# Connector_0.net
KiCad netlist of a schematic drawn in Altium Designer
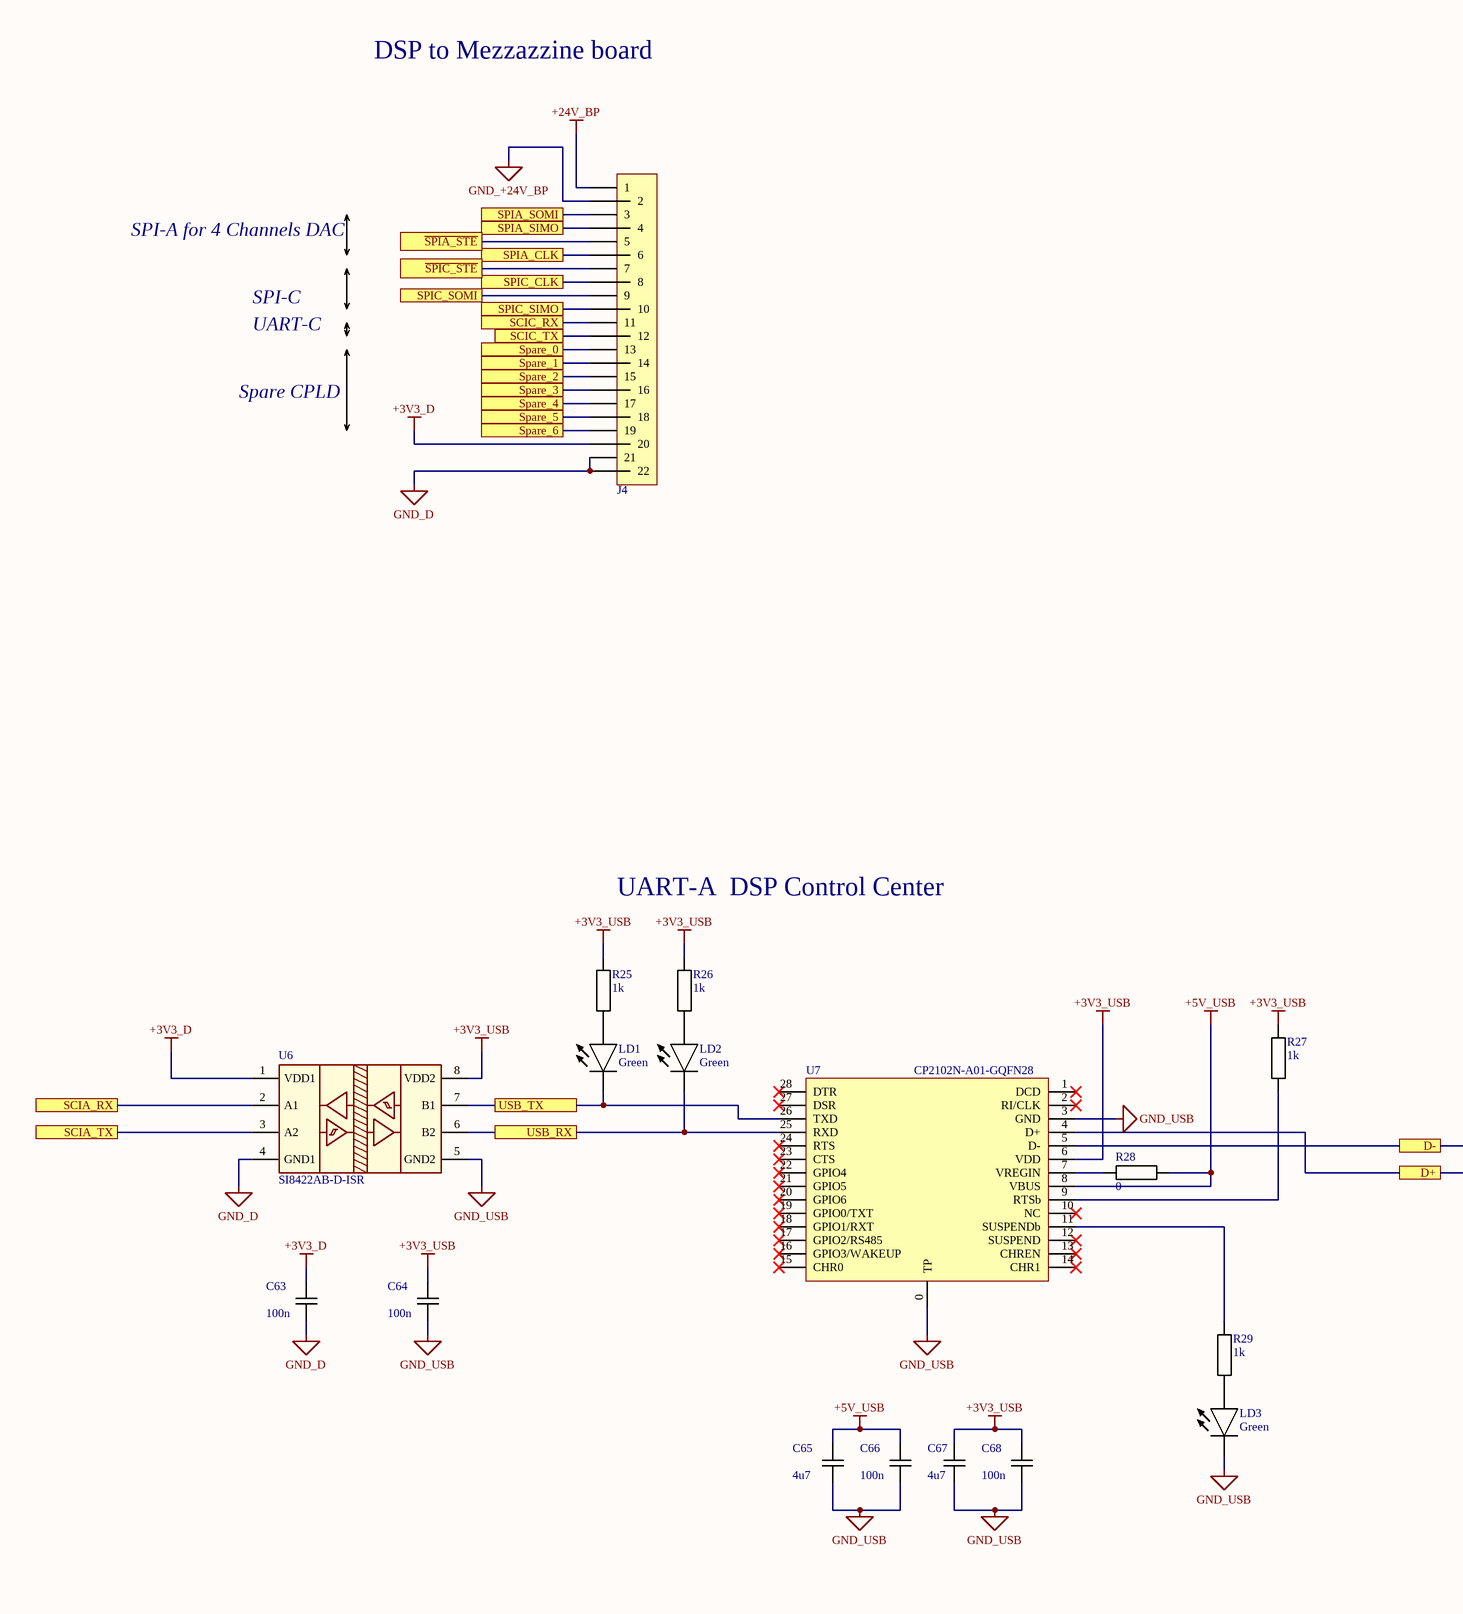
[diagram p0: Connector_0.SchDoc, left]
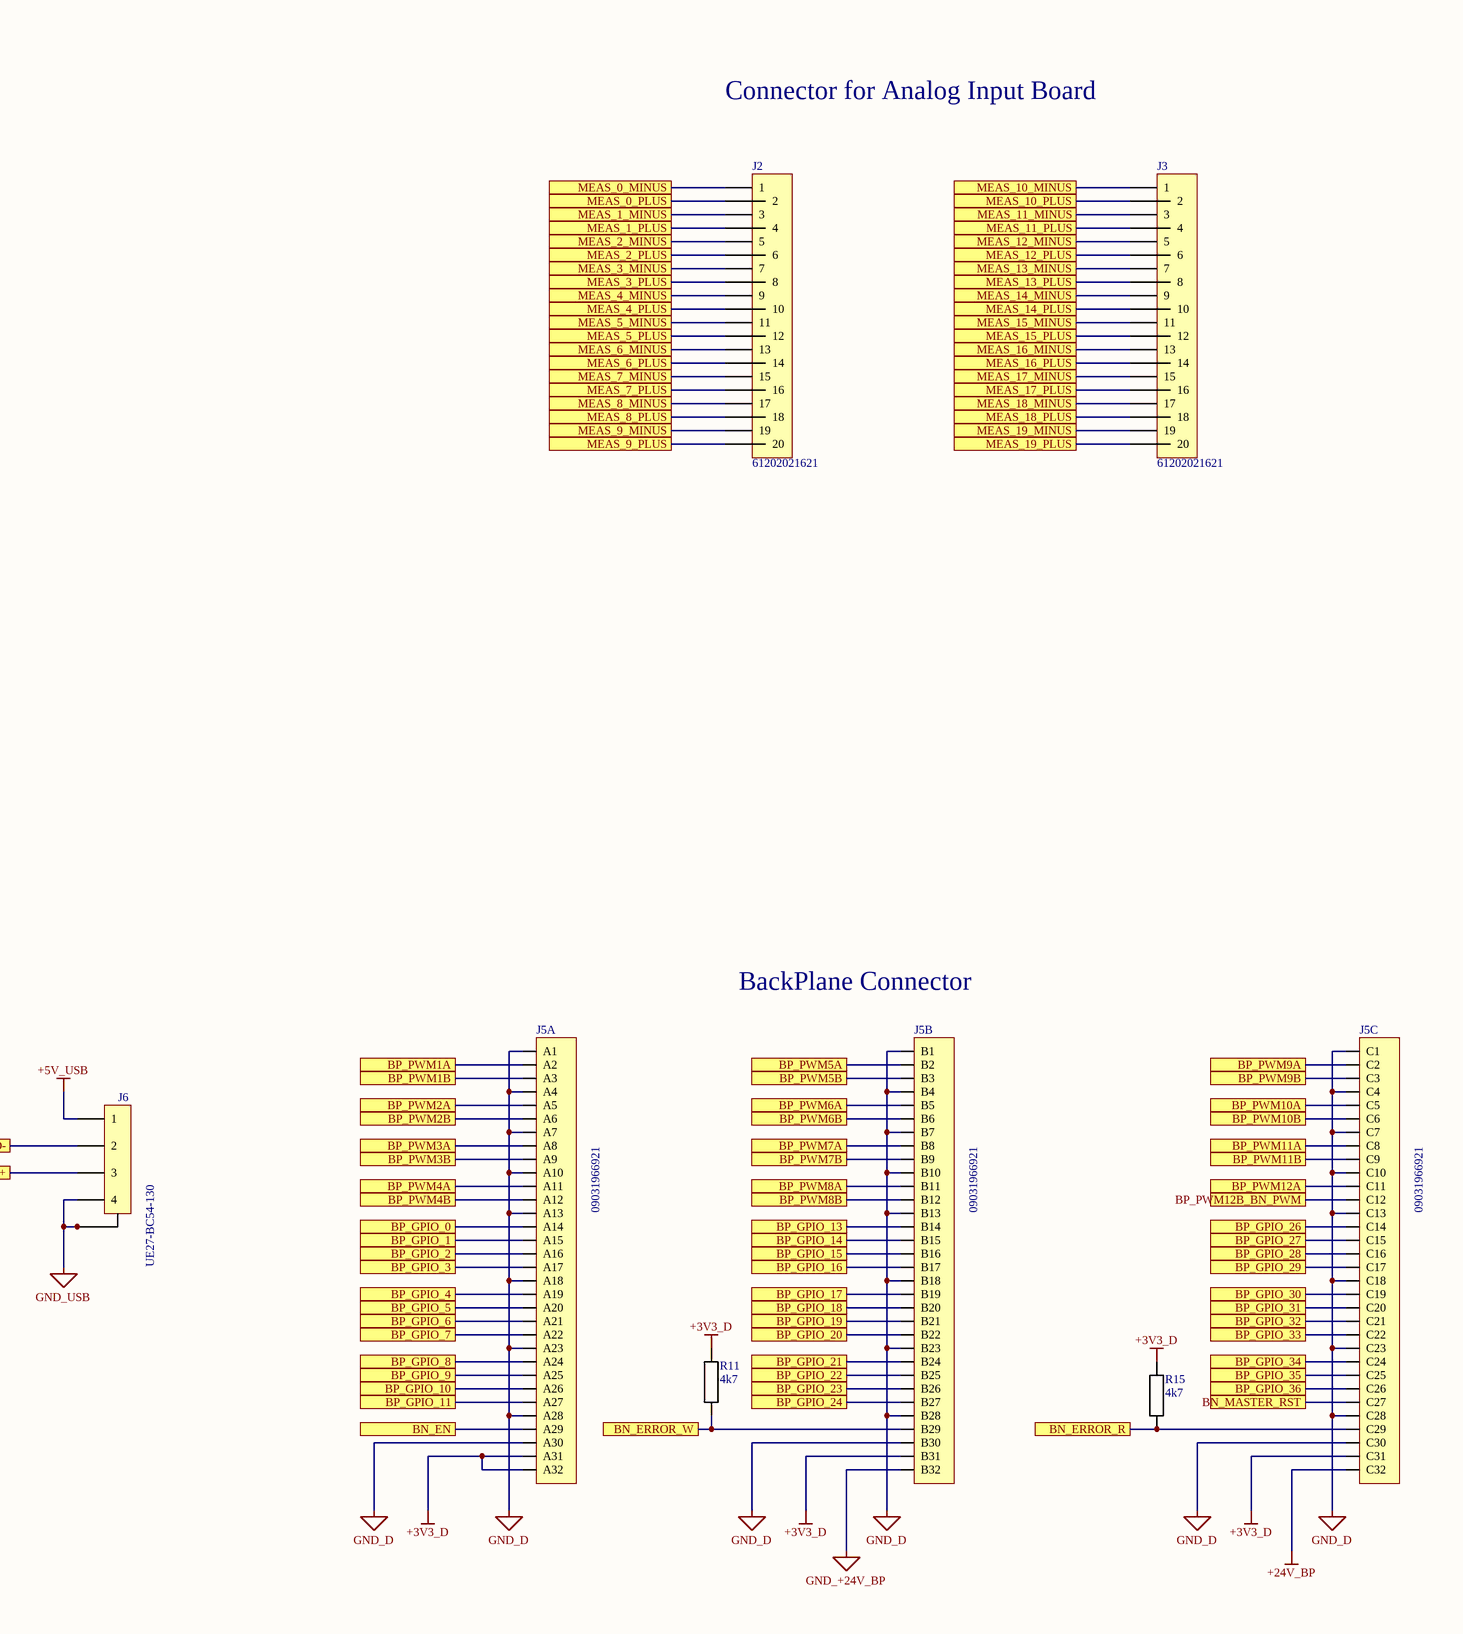
[diagram p1: Connector_0.SchDoc, right]

(export (version "E")
  (design (tool "Eeschema 10.0.6"))
  (components
    (comp (ref "C63")
      (value "100n")
      (footprint "CAPACITOR 1608 REFLOW")
      (description "Capacitor X7R 10% 50V 1608(0603)")
      (libsource (lib "Capacitor") (part "Capacitor"))
    )
    (comp (ref "C64")
      (value "100n")
      (footprint "CAPACITOR 1608 REFLOW")
      (description "Capacitor X7R 10% 50V 1608(0603)")
      (libsource (lib "Capacitor") (part "Capacitor"))
    )
    (comp (ref "C65")
      (value "4u7")
      (footprint "CAPACITOR 2012 REFLOW")
      (description "Capacitor X7R 10% 10V 2012(0805)")
      (libsource (lib "Capacitor") (part "Capacitor"))
    )
    (comp (ref "C66")
      (value "100n")
      (footprint "CAPACITOR 1608 REFLOW")
      (description "Capacitor X7R 10% 50V 1608(0603)")
      (libsource (lib "Capacitor") (part "Capacitor"))
    )
    (comp (ref "C67")
      (value "4u7")
      (footprint "CAPACITOR 2012 REFLOW")
      (description "Capacitor X7R 10% 10V 2012(0805)")
      (libsource (lib "Capacitor") (part "Capacitor"))
    )
    (comp (ref "C68")
      (value "100n")
      (footprint "CAPACITOR 1608 REFLOW")
      (description "Capacitor X7R 10% 50V 1608(0603)")
      (libsource (lib "Capacitor") (part "Capacitor"))
    )
    (comp (ref "J2")
      (value "61202021621")
      (footprint "FlatCable2x10 2.54MM Straight TH")
      (description "FlatCable2x10")
      (fields (field (name "MANUFACTURER") "Wurth Elektronik"))
      (libsource (lib "Connector") (part "FlatCable2x10"))
    )
    (comp (ref "J3")
      (value "61202021621")
      (footprint "FlatCable2x10 2.54MM Straight TH")
      (description "FlatCable2x10")
      (fields (field (name "MANUFACTURER") "Wurth Elektronik"))
      (libsource (lib "Connector") (part "FlatCable2x10"))
    )
    (comp (ref "J4")
      (value "*")
      (footprint "PinHeader2x11 P2.54 A")
      (description "Plug connector")
      (libsource (lib "PinHeader") (part "PinHeader2x11"))
    )
    (comp (ref "J5")
      (value "09031966921")
      (footprint "DIN41612 MALE 3X32 ABC R90")
      (description "DIN41612 MALE 3X32 ABC R90")
      (fields (field (name "MANUFACTURER") "Harting"))
      (libsource (lib "Connector") (part "DIN41612 MALE 3X32 ABC R90"))
    )
    (comp (ref "J6")
      (value "UE27-BC54-130")
      (footprint "USB-B TH AMPHENOL UE27-BC54-130")
      (description "USB-B-TH-AMPHENOL UE27-BC54-130")
      (fields (field (name "MANUFACTURER") "Amphenol ICC"))
      (libsource (lib "Connector") (part "USB-B-TH-AMPHENOL UE27-BC54-130"))
    )
    (comp (ref "LD1")
      (value "Green")
      (footprint "LED 2012 REFLOW")
      (description "LED generic")
      (libsource (lib "Diode") (part "LED"))
    )
    (comp (ref "LD2")
      (value "Green")
      (footprint "LED 2012 REFLOW")
      (description "LED generic")
      (libsource (lib "Diode") (part "LED"))
    )
    (comp (ref "LD3")
      (value "Green")
      (footprint "LED 2012 REFLOW")
      (description "LED generic")
      (libsource (lib "Diode") (part "LED"))
    )
    (comp (ref "R11")
      (value "4k7")
      (footprint "RESISTOR 1608 REFLOW")
      (description "Resistor 1% 50V 100mW 1608(0603)")
      (libsource (lib "Resistor") (part "Resistor"))
    )
    (comp (ref "R15")
      (value "4k7")
      (footprint "RESISTOR 1608 REFLOW")
      (description "Resistor 1% 50V 100mW 1608(0603)")
      (libsource (lib "Resistor") (part "Resistor"))
    )
    (comp (ref "R25")
      (value "1k")
      (footprint "RESISTOR 1608 REFLOW")
      (description "Resistor 1% 50V 100mW 1608(0603)")
      (libsource (lib "Resistor") (part "Resistor"))
    )
    (comp (ref "R26")
      (value "1k")
      (footprint "RESISTOR 1608 REFLOW")
      (description "Resistor 1% 50V 100mW 1608(0603)")
      (libsource (lib "Resistor") (part "Resistor"))
    )
    (comp (ref "R27")
      (value "1k")
      (footprint "RESISTOR 1608 REFLOW")
      (description "Resistor 1% 50V 100mW 1608(0603)")
      (libsource (lib "Resistor") (part "Resistor"))
    )
    (comp (ref "R28")
      (value "0")
      (footprint "RESISTOR 1608 REFLOW")
      (description "Resistor 1% 50V 100mW 1608(0603)")
      (libsource (lib "Resistor") (part "Resistor"))
    )
    (comp (ref "R29")
      (value "1k")
      (footprint "RESISTOR 1608 REFLOW")
      (description "Resistor 1% 50V 100mW 1608(0603)")
      (libsource (lib "Resistor") (part "Resistor"))
    )
    (comp (ref "U6")
      (value "SI8422AB-D-ISR")
      (footprint "SO8 P1.27 C4.0X5.0 H1.75")
      (description "Optocoupler")
      (fields (field (name "MANUFACTURER") "Silicon Labs"))
      (libsource (lib "Optocoupler") (part "SI8422"))
    )
    (comp (ref "U7")
      (value "CP2102N-A01-GQFN28")
      (footprint "QFN28 P0.5 T3.4X3.4 C5.0X5.0 H0.8")
      (description "USBXpress")
      (fields (field (name "MANUFACTURER") "Silicon Labs"))
      (libsource (lib "IntegratedCircuit") (part "CP2102N"))
    )
  )
  (nets
    (net (code "1") (name "+3V3_D") (class "Default")
      (node (ref "C63") (pin "2") (pinfunction "2_2") (pintype "passive"))
      (node (ref "J4") (pin "20") (pinfunction "20_20") (pintype "passive"))
      (node (ref "J5") (pin "A31") (pinfunction "A31_A31") (pintype "passive"))
      (node (ref "J5") (pin "A32") (pinfunction "A32_A32") (pintype "passive"))
      (node (ref "J5") (pin "B31") (pinfunction "B31_B31") (pintype "passive"))
      (node (ref "J5") (pin "C31") (pinfunction "C31_C31") (pintype "passive"))
      (node (ref "R11") (pin "2") (pinfunction "2_2") (pintype "passive"))
      (node (ref "R15") (pin "2") (pinfunction "2_2") (pintype "passive"))
      (node (ref "U6") (pin "1") (pinfunction "VDD1_1") (pintype "passive"))
    )
    (net (code "2") (name "+3V3_USB") (class "Default")
      (node (ref "C64") (pin "2") (pinfunction "2_2") (pintype "passive"))
      (node (ref "C67") (pin "2") (pinfunction "2_2") (pintype "passive"))
      (node (ref "C68") (pin "2") (pinfunction "2_2") (pintype "passive"))
      (node (ref "R25") (pin "2") (pinfunction "2_2") (pintype "passive"))
      (node (ref "R26") (pin "2") (pinfunction "2_2") (pintype "passive"))
      (node (ref "R27") (pin "2") (pinfunction "2_2") (pintype "passive"))
      (node (ref "U6") (pin "8") (pinfunction "VDD2_8") (pintype "power_in"))
      (node (ref "U7") (pin "6") (pinfunction "VDD_6") (pintype "passive"))
    )
    (net (code "3") (name "+5V_USB") (class "Default")
      (node (ref "C65") (pin "2") (pinfunction "2_2") (pintype "passive"))
      (node (ref "C66") (pin "2") (pinfunction "2_2") (pintype "passive"))
      (node (ref "J6") (pin "1") (pinfunction "1_1") (pintype "passive"))
      (node (ref "R28") (pin "1") (pinfunction "1_1") (pintype "passive"))
      (node (ref "U7") (pin "8") (pinfunction "VBUS_8") (pintype "passive"))
    )
    (net (code "4") (name "+24V_BP") (class "Default")
      (node (ref "J4") (pin "1") (pinfunction "1_1") (pintype "passive"))
      (node (ref "J5") (pin "C32") (pinfunction "C32_C32") (pintype "passive"))
    )
    (net (code "5") (name "/BN_EN") (class "Default")
      (node (ref "J5") (pin "A29") (pinfunction "A29_A29") (pintype "passive"))
    )
    (net (code "6") (name "/BN_ERROR_R") (class "Default")
      (node (ref "J5") (pin "C29") (pinfunction "C29_C29") (pintype "passive"))
      (node (ref "R15") (pin "1") (pinfunction "1_1") (pintype "passive"))
    )
    (net (code "7") (name "/BN_ERROR_W") (class "Default")
      (node (ref "J5") (pin "B29") (pinfunction "B29_B29") (pintype "passive"))
      (node (ref "R11") (pin "1") (pinfunction "1_1") (pintype "passive"))
    )
    (net (code "8") (name "/BN_MASTER_RST") (class "Default")
      (node (ref "J5") (pin "C27") (pinfunction "C27_C27") (pintype "passive"))
    )
    (net (code "9") (name "/BP_GPIO_0") (class "Default")
      (node (ref "J5") (pin "A14") (pinfunction "A14_A14") (pintype "passive"))
    )
    (net (code "10") (name "/BP_GPIO_1") (class "Default")
      (node (ref "J5") (pin "A15") (pinfunction "A15_A15") (pintype "passive"))
    )
    (net (code "11") (name "/BP_GPIO_2") (class "Default")
      (node (ref "J5") (pin "A16") (pinfunction "A16_A16") (pintype "passive"))
    )
    (net (code "12") (name "/BP_GPIO_3") (class "Default")
      (node (ref "J5") (pin "A17") (pinfunction "A17_A17") (pintype "passive"))
    )
    (net (code "13") (name "/BP_GPIO_4") (class "Default")
      (node (ref "J5") (pin "A19") (pinfunction "A19_A19") (pintype "passive"))
    )
    (net (code "14") (name "/BP_GPIO_5") (class "Default")
      (node (ref "J5") (pin "A20") (pinfunction "A20_A20") (pintype "passive"))
    )
    (net (code "15") (name "/BP_GPIO_6") (class "Default")
      (node (ref "J5") (pin "A21") (pinfunction "A21_A21") (pintype "passive"))
    )
    (net (code "16") (name "/BP_GPIO_7") (class "Default")
      (node (ref "J5") (pin "A22") (pinfunction "A22_A22") (pintype "passive"))
    )
    (net (code "17") (name "/BP_GPIO_8") (class "Default")
      (node (ref "J5") (pin "A24") (pinfunction "A24_A24") (pintype "passive"))
    )
    (net (code "18") (name "/BP_GPIO_9") (class "Default")
      (node (ref "J5") (pin "A25") (pinfunction "A25_A25") (pintype "passive"))
    )
    (net (code "19") (name "/BP_GPIO_10") (class "Default")
      (node (ref "J5") (pin "A26") (pinfunction "A26_A26") (pintype "passive"))
    )
    (net (code "20") (name "/BP_GPIO_11") (class "Default")
      (node (ref "J5") (pin "A27") (pinfunction "A27_A27") (pintype "passive"))
    )
    (net (code "21") (name "/BP_GPIO_13") (class "Default")
      (node (ref "J5") (pin "B14") (pinfunction "B14_B14") (pintype "passive"))
    )
    (net (code "22") (name "/BP_GPIO_14") (class "Default")
      (node (ref "J5") (pin "B15") (pinfunction "B15_B15") (pintype "passive"))
    )
    (net (code "23") (name "/BP_GPIO_15") (class "Default")
      (node (ref "J5") (pin "B16") (pinfunction "B16_B16") (pintype "passive"))
    )
    (net (code "24") (name "/BP_GPIO_16") (class "Default")
      (node (ref "J5") (pin "B17") (pinfunction "B17_B17") (pintype "passive"))
    )
    (net (code "25") (name "/BP_GPIO_17") (class "Default")
      (node (ref "J5") (pin "B19") (pinfunction "B19_B19") (pintype "passive"))
    )
    (net (code "26") (name "/BP_GPIO_18") (class "Default")
      (node (ref "J5") (pin "B20") (pinfunction "B20_B20") (pintype "passive"))
    )
    (net (code "27") (name "/BP_GPIO_19") (class "Default")
      (node (ref "J5") (pin "B21") (pinfunction "B21_B21") (pintype "passive"))
    )
    (net (code "28") (name "/BP_GPIO_20") (class "Default")
      (node (ref "J5") (pin "B22") (pinfunction "B22_B22") (pintype "passive"))
    )
    (net (code "29") (name "/BP_GPIO_21") (class "Default")
      (node (ref "J5") (pin "B24") (pinfunction "B24_B24") (pintype "passive"))
    )
    (net (code "30") (name "/BP_GPIO_22") (class "Default")
      (node (ref "J5") (pin "B25") (pinfunction "B25_B25") (pintype "passive"))
    )
    (net (code "31") (name "/BP_GPIO_23") (class "Default")
      (node (ref "J5") (pin "B26") (pinfunction "B26_B26") (pintype "passive"))
    )
    (net (code "32") (name "/BP_GPIO_24") (class "Default")
      (node (ref "J5") (pin "B27") (pinfunction "B27_B27") (pintype "passive"))
    )
    (net (code "33") (name "/BP_GPIO_26") (class "Default")
      (node (ref "J5") (pin "C14") (pinfunction "C14_C14") (pintype "passive"))
    )
    (net (code "34") (name "/BP_GPIO_27") (class "Default")
      (node (ref "J5") (pin "C15") (pinfunction "C15_C15") (pintype "passive"))
    )
    (net (code "35") (name "/BP_GPIO_28") (class "Default")
      (node (ref "J5") (pin "C16") (pinfunction "C16_C16") (pintype "passive"))
    )
    (net (code "36") (name "/BP_GPIO_29") (class "Default")
      (node (ref "J5") (pin "C17") (pinfunction "C17_C17") (pintype "passive"))
    )
    (net (code "37") (name "/BP_GPIO_30") (class "Default")
      (node (ref "J5") (pin "C19") (pinfunction "C19_C19") (pintype "passive"))
    )
    (net (code "38") (name "/BP_GPIO_31") (class "Default")
      (node (ref "J5") (pin "C20") (pinfunction "C20_C20") (pintype "passive"))
    )
    (net (code "39") (name "/BP_GPIO_32") (class "Default")
      (node (ref "J5") (pin "C21") (pinfunction "C21_C21") (pintype "passive"))
    )
    (net (code "40") (name "/BP_GPIO_33") (class "Default")
      (node (ref "J5") (pin "C22") (pinfunction "C22_C22") (pintype "passive"))
    )
    (net (code "41") (name "/BP_GPIO_34") (class "Default")
      (node (ref "J5") (pin "C24") (pinfunction "C24_C24") (pintype "passive"))
    )
    (net (code "42") (name "/BP_GPIO_35") (class "Default")
      (node (ref "J5") (pin "C25") (pinfunction "C25_C25") (pintype "passive"))
    )
    (net (code "43") (name "/BP_GPIO_36") (class "Default")
      (node (ref "J5") (pin "C26") (pinfunction "C26_C26") (pintype "passive"))
    )
    (net (code "44") (name "/BP_PWM1A") (class "Default")
      (node (ref "J5") (pin "A2") (pinfunction "A2_A2") (pintype "passive"))
    )
    (net (code "45") (name "/BP_PWM1B") (class "Default")
      (node (ref "J5") (pin "A3") (pinfunction "A3_A3") (pintype "passive"))
    )
    (net (code "46") (name "/BP_PWM2A") (class "Default")
      (node (ref "J5") (pin "A5") (pinfunction "A5_A5") (pintype "passive"))
    )
    (net (code "47") (name "/BP_PWM2B") (class "Default")
      (node (ref "J5") (pin "A6") (pinfunction "A6_A6") (pintype "passive"))
    )
    (net (code "48") (name "/BP_PWM3A") (class "Default")
      (node (ref "J5") (pin "A8") (pinfunction "A8_A8") (pintype "passive"))
    )
    (net (code "49") (name "/BP_PWM3B") (class "Default")
      (node (ref "J5") (pin "A9") (pinfunction "A9_A9") (pintype "passive"))
    )
    (net (code "50") (name "/BP_PWM4A") (class "Default")
      (node (ref "J5") (pin "A11") (pinfunction "A11_A11") (pintype "passive"))
    )
    (net (code "51") (name "/BP_PWM4B") (class "Default")
      (node (ref "J5") (pin "A12") (pinfunction "A12_A12") (pintype "passive"))
    )
    (net (code "52") (name "/BP_PWM5A") (class "Default")
      (node (ref "J5") (pin "B2") (pinfunction "B2_B2") (pintype "passive"))
    )
    (net (code "53") (name "/BP_PWM5B") (class "Default")
      (node (ref "J5") (pin "B3") (pinfunction "B3_B3") (pintype "passive"))
    )
    (net (code "54") (name "/BP_PWM6A") (class "Default")
      (node (ref "J5") (pin "B5") (pinfunction "B5_B5") (pintype "passive"))
    )
    (net (code "55") (name "/BP_PWM6B") (class "Default")
      (node (ref "J5") (pin "B6") (pinfunction "B6_B6") (pintype "passive"))
    )
    (net (code "56") (name "/BP_PWM7A") (class "Default")
      (node (ref "J5") (pin "B8") (pinfunction "B8_B8") (pintype "passive"))
    )
    (net (code "57") (name "/BP_PWM7B") (class "Default")
      (node (ref "J5") (pin "B9") (pinfunction "B9_B9") (pintype "passive"))
    )
    (net (code "58") (name "/BP_PWM8A") (class "Default")
      (node (ref "J5") (pin "B11") (pinfunction "B11_B11") (pintype "passive"))
    )
    (net (code "59") (name "/BP_PWM8B") (class "Default")
      (node (ref "J5") (pin "B12") (pinfunction "B12_B12") (pintype "passive"))
    )
    (net (code "60") (name "/BP_PWM9A") (class "Default")
      (node (ref "J5") (pin "C2") (pinfunction "C2_C2") (pintype "passive"))
    )
    (net (code "61") (name "/BP_PWM9B") (class "Default")
      (node (ref "J5") (pin "C3") (pinfunction "C3_C3") (pintype "passive"))
    )
    (net (code "62") (name "/BP_PWM10A") (class "Default")
      (node (ref "J5") (pin "C5") (pinfunction "C5_C5") (pintype "passive"))
    )
    (net (code "63") (name "/BP_PWM10B") (class "Default")
      (node (ref "J5") (pin "C6") (pinfunction "C6_C6") (pintype "passive"))
    )
    (net (code "64") (name "/BP_PWM11A") (class "Default")
      (node (ref "J5") (pin "C8") (pinfunction "C8_C8") (pintype "passive"))
    )
    (net (code "65") (name "/BP_PWM11B") (class "Default")
      (node (ref "J5") (pin "C9") (pinfunction "C9_C9") (pintype "passive"))
    )
    (net (code "66") (name "/BP_PWM12A") (class "Default")
      (node (ref "J5") (pin "C11") (pinfunction "C11_C11") (pintype "passive"))
    )
    (net (code "67") (name "/BP_PWM12B_BN_PWM") (class "Default")
      (node (ref "J5") (pin "C12") (pinfunction "C12_C12") (pintype "passive"))
    )
    (net (code "68") (name "/D+") (class "Default")
      (node (ref "J6") (pin "3") (pinfunction "3_3") (pintype "passive"))
      (node (ref "U7") (pin "4") (pinfunction "D+_4") (pintype "passive"))
    )
    (net (code "69") (name "/D-") (class "Default")
      (node (ref "J6") (pin "2") (pinfunction "2_2") (pintype "passive"))
      (node (ref "U7") (pin "5") (pinfunction "D-_5") (pintype "passive"))
    )
    (net (code "70") (name "/MEAS_0_MINUS") (class "Default")
      (node (ref "J2") (pin "1") (pinfunction "1_1") (pintype "passive"))
    )
    (net (code "71") (name "/MEAS_0_PLUS") (class "Default")
      (node (ref "J2") (pin "2") (pinfunction "2_2") (pintype "passive"))
    )
    (net (code "72") (name "/MEAS_1_MINUS") (class "Default")
      (node (ref "J2") (pin "3") (pinfunction "3_3") (pintype "passive"))
    )
    (net (code "73") (name "/MEAS_1_PLUS") (class "Default")
      (node (ref "J2") (pin "4") (pinfunction "4_4") (pintype "passive"))
    )
    (net (code "74") (name "/MEAS_2_MINUS") (class "Default")
      (node (ref "J2") (pin "5") (pinfunction "5_5") (pintype "passive"))
    )
    (net (code "75") (name "/MEAS_2_PLUS") (class "Default")
      (node (ref "J2") (pin "6") (pinfunction "6_6") (pintype "passive"))
    )
    (net (code "76") (name "/MEAS_3_MINUS") (class "Default")
      (node (ref "J2") (pin "7") (pinfunction "7_7") (pintype "passive"))
    )
    (net (code "77") (name "/MEAS_3_PLUS") (class "Default")
      (node (ref "J2") (pin "8") (pinfunction "8_8") (pintype "passive"))
    )
    (net (code "78") (name "/MEAS_4_MINUS") (class "Default")
      (node (ref "J2") (pin "9") (pinfunction "9_9") (pintype "passive"))
    )
    (net (code "79") (name "/MEAS_4_PLUS") (class "Default")
      (node (ref "J2") (pin "10") (pinfunction "10_10") (pintype "passive"))
    )
    (net (code "80") (name "/MEAS_5_MINUS") (class "Default")
      (node (ref "J2") (pin "11") (pinfunction "11_11") (pintype "passive"))
    )
    (net (code "81") (name "/MEAS_5_PLUS") (class "Default")
      (node (ref "J2") (pin "12") (pinfunction "12_12") (pintype "passive"))
    )
    (net (code "82") (name "/MEAS_6_MINUS") (class "Default")
      (node (ref "J2") (pin "13") (pinfunction "13_13") (pintype "passive"))
    )
    (net (code "83") (name "/MEAS_6_PLUS") (class "Default")
      (node (ref "J2") (pin "14") (pinfunction "14_14") (pintype "passive"))
    )
    (net (code "84") (name "/MEAS_7_MINUS") (class "Default")
      (node (ref "J2") (pin "15") (pinfunction "15_15") (pintype "passive"))
    )
    (net (code "85") (name "/MEAS_7_PLUS") (class "Default")
      (node (ref "J2") (pin "16") (pinfunction "16_16") (pintype "passive"))
    )
    (net (code "86") (name "/MEAS_8_MINUS") (class "Default")
      (node (ref "J2") (pin "17") (pinfunction "17_17") (pintype "passive"))
    )
    (net (code "87") (name "/MEAS_8_PLUS") (class "Default")
      (node (ref "J2") (pin "18") (pinfunction "18_18") (pintype "passive"))
    )
    (net (code "88") (name "/MEAS_9_MINUS") (class "Default")
      (node (ref "J2") (pin "19") (pinfunction "19_19") (pintype "passive"))
    )
    (net (code "89") (name "/MEAS_9_PLUS") (class "Default")
      (node (ref "J2") (pin "20") (pinfunction "20_20") (pintype "passive"))
    )
    (net (code "90") (name "/MEAS_10_MINUS") (class "Default")
      (node (ref "J3") (pin "1") (pinfunction "1_1") (pintype "passive"))
    )
    (net (code "91") (name "/MEAS_10_PLUS") (class "Default")
      (node (ref "J3") (pin "2") (pinfunction "2_2") (pintype "passive"))
    )
    (net (code "92") (name "/MEAS_11_MINUS") (class "Default")
      (node (ref "J3") (pin "3") (pinfunction "3_3") (pintype "passive"))
    )
    (net (code "93") (name "/MEAS_11_PLUS") (class "Default")
      (node (ref "J3") (pin "4") (pinfunction "4_4") (pintype "passive"))
    )
    (net (code "94") (name "/MEAS_12_MINUS") (class "Default")
      (node (ref "J3") (pin "5") (pinfunction "5_5") (pintype "passive"))
    )
    (net (code "95") (name "/MEAS_12_PLUS") (class "Default")
      (node (ref "J3") (pin "6") (pinfunction "6_6") (pintype "passive"))
    )
    (net (code "96") (name "/MEAS_13_MINUS") (class "Default")
      (node (ref "J3") (pin "7") (pinfunction "7_7") (pintype "passive"))
    )
    (net (code "97") (name "/MEAS_13_PLUS") (class "Default")
      (node (ref "J3") (pin "8") (pinfunction "8_8") (pintype "passive"))
    )
    (net (code "98") (name "/MEAS_14_MINUS") (class "Default")
      (node (ref "J3") (pin "9") (pinfunction "9_9") (pintype "passive"))
    )
    (net (code "99") (name "/MEAS_14_PLUS") (class "Default")
      (node (ref "J3") (pin "10") (pinfunction "10_10") (pintype "passive"))
    )
    (net (code "100") (name "/MEAS_15_MINUS") (class "Default")
      (node (ref "J3") (pin "11") (pinfunction "11_11") (pintype "passive"))
    )
    (net (code "101") (name "/MEAS_15_PLUS") (class "Default")
      (node (ref "J3") (pin "12") (pinfunction "12_12") (pintype "passive"))
    )
    (net (code "102") (name "/MEAS_16_MINUS") (class "Default")
      (node (ref "J3") (pin "13") (pinfunction "13_13") (pintype "passive"))
    )
    (net (code "103") (name "/MEAS_16_PLUS") (class "Default")
      (node (ref "J3") (pin "14") (pinfunction "14_14") (pintype "passive"))
    )
    (net (code "104") (name "/MEAS_17_MINUS") (class "Default")
      (node (ref "J3") (pin "15") (pinfunction "15_15") (pintype "passive"))
    )
    (net (code "105") (name "/MEAS_17_PLUS") (class "Default")
      (node (ref "J3") (pin "16") (pinfunction "16_16") (pintype "passive"))
    )
    (net (code "106") (name "/MEAS_18_MINUS") (class "Default")
      (node (ref "J3") (pin "17") (pinfunction "17_17") (pintype "passive"))
    )
    (net (code "107") (name "/MEAS_18_PLUS") (class "Default")
      (node (ref "J3") (pin "18") (pinfunction "18_18") (pintype "passive"))
    )
    (net (code "108") (name "/MEAS_19_MINUS") (class "Default")
      (node (ref "J3") (pin "19") (pinfunction "19_19") (pintype "passive"))
    )
    (net (code "109") (name "/MEAS_19_PLUS") (class "Default")
      (node (ref "J3") (pin "20") (pinfunction "20_20") (pintype "passive"))
    )
    (net (code "110") (name "/SCIA_RX") (class "Default")
      (node (ref "U6") (pin "2") (pinfunction "A1_2") (pintype "passive"))
    )
    (net (code "111") (name "/SCIA_TX") (class "Default")
      (node (ref "U6") (pin "3") (pinfunction "A2_3") (pintype "passive"))
    )
    (net (code "112") (name "/SCIC_RX") (class "Default")
      (node (ref "J4") (pin "11") (pinfunction "11_11") (pintype "passive"))
    )
    (net (code "113") (name "/SCIC_TX") (class "Default")
      (node (ref "J4") (pin "12") (pinfunction "12_12") (pintype "passive"))
    )
    (net (code "114") (name "/SPIA_CLK") (class "Default")
      (node (ref "J4") (pin "6") (pinfunction "6_6") (pintype "passive"))
    )
    (net (code "115") (name "/SPIA_SIMO") (class "Default")
      (node (ref "J4") (pin "4") (pinfunction "4_4") (pintype "passive"))
    )
    (net (code "116") (name "/SPIA_SOMI") (class "Default")
      (node (ref "J4") (pin "3") (pinfunction "3_3") (pintype "passive"))
    )
    (net (code "117") (name "/SPIC_CLK") (class "Default")
      (node (ref "J4") (pin "8") (pinfunction "8_8") (pintype "passive"))
    )
    (net (code "118") (name "/SPIC_SIMO") (class "Default")
      (node (ref "J4") (pin "10") (pinfunction "10_10") (pintype "passive"))
    )
    (net (code "119") (name "/SPIC_SOMI") (class "Default")
      (node (ref "J4") (pin "9") (pinfunction "9_9") (pintype "passive"))
    )
    (net (code "120") (name "/Spare_0") (class "Default")
      (node (ref "J4") (pin "13") (pinfunction "13_13") (pintype "passive"))
    )
    (net (code "121") (name "/Spare_1") (class "Default")
      (node (ref "J4") (pin "14") (pinfunction "14_14") (pintype "passive"))
    )
    (net (code "122") (name "/Spare_2") (class "Default")
      (node (ref "J4") (pin "15") (pinfunction "15_15") (pintype "passive"))
    )
    (net (code "123") (name "/Spare_3") (class "Default")
      (node (ref "J4") (pin "16") (pinfunction "16_16") (pintype "passive"))
    )
    (net (code "124") (name "/Spare_4") (class "Default")
      (node (ref "J4") (pin "17") (pinfunction "17_17") (pintype "passive"))
    )
    (net (code "125") (name "/Spare_5") (class "Default")
      (node (ref "J4") (pin "18") (pinfunction "18_18") (pintype "passive"))
    )
    (net (code "126") (name "/Spare_6") (class "Default")
      (node (ref "J4") (pin "19") (pinfunction "19_19") (pintype "passive"))
    )
    (net (code "127") (name "/USB_RX") (class "Default")
      (node (ref "LD2") (pin "1") (pinfunction "C_1") (pintype "passive"))
      (node (ref "U6") (pin "6") (pinfunction "B2_6") (pintype "passive"))
      (node (ref "U7") (pin "25") (pinfunction "RXD_25") (pintype "passive"))
    )
    (net (code "128") (name "/USB_TX") (class "Default")
      (node (ref "LD1") (pin "1") (pinfunction "C_1") (pintype "passive"))
      (node (ref "U6") (pin "7") (pinfunction "B1_7") (pintype "passive"))
      (node (ref "U7") (pin "26") (pinfunction "TXD_26") (pintype "passive"))
    )
    (net (code "129") (name "/~{SPIA_STE}") (class "Default")
      (node (ref "J4") (pin "5") (pinfunction "5_5") (pintype "passive"))
    )
    (net (code "130") (name "/~{SPIC_STE}") (class "Default")
      (node (ref "J4") (pin "7") (pinfunction "7_7") (pintype "passive"))
    )
    (net (code "131") (name "GND_+24V_BP") (class "Default")
      (node (ref "J4") (pin "2") (pinfunction "2_2") (pintype "passive"))
      (node (ref "J5") (pin "B32") (pinfunction "B32_B32") (pintype "passive"))
    )
    (net (code "132") (name "GND_D") (class "Default")
      (node (ref "C63") (pin "1") (pinfunction "1_1") (pintype "passive"))
      (node (ref "J4") (pin "21") (pinfunction "21_21") (pintype "passive"))
      (node (ref "J4") (pin "22") (pinfunction "22_22") (pintype "passive"))
      (node (ref "J5") (pin "A1") (pinfunction "A1_A1") (pintype "passive"))
      (node (ref "J5") (pin "A10") (pinfunction "A10_A10") (pintype "passive"))
      (node (ref "J5") (pin "A13") (pinfunction "A13_A13") (pintype "passive"))
      (node (ref "J5") (pin "A18") (pinfunction "A18_A18") (pintype "passive"))
      (node (ref "J5") (pin "A23") (pinfunction "A23_A23") (pintype "passive"))
      (node (ref "J5") (pin "A28") (pinfunction "A28_A28") (pintype "passive"))
      (node (ref "J5") (pin "A30") (pinfunction "A30_A30") (pintype "passive"))
      (node (ref "J5") (pin "A4") (pinfunction "A4_A4") (pintype "passive"))
      (node (ref "J5") (pin "A7") (pinfunction "A7_A7") (pintype "passive"))
      (node (ref "J5") (pin "B1") (pinfunction "B1_B1") (pintype "passive"))
      (node (ref "J5") (pin "B10") (pinfunction "B10_B10") (pintype "passive"))
      (node (ref "J5") (pin "B13") (pinfunction "B13_B13") (pintype "passive"))
      (node (ref "J5") (pin "B18") (pinfunction "B18_B18") (pintype "passive"))
      (node (ref "J5") (pin "B23") (pinfunction "B23_B23") (pintype "passive"))
      (node (ref "J5") (pin "B28") (pinfunction "B28_B28") (pintype "passive"))
      (node (ref "J5") (pin "B30") (pinfunction "B30_B30") (pintype "passive"))
      (node (ref "J5") (pin "B4") (pinfunction "B4_B4") (pintype "passive"))
      (node (ref "J5") (pin "B7") (pinfunction "B7_B7") (pintype "passive"))
      (node (ref "J5") (pin "C1") (pinfunction "C1_C1") (pintype "passive"))
      (node (ref "J5") (pin "C10") (pinfunction "C10_C10") (pintype "passive"))
      (node (ref "J5") (pin "C13") (pinfunction "C13_C13") (pintype "passive"))
      (node (ref "J5") (pin "C18") (pinfunction "C18_C18") (pintype "passive"))
      (node (ref "J5") (pin "C23") (pinfunction "C23_C23") (pintype "passive"))
      (node (ref "J5") (pin "C28") (pinfunction "C28_C28") (pintype "passive"))
      (node (ref "J5") (pin "C30") (pinfunction "C30_C30") (pintype "passive"))
      (node (ref "J5") (pin "C4") (pinfunction "C4_C4") (pintype "passive"))
      (node (ref "J5") (pin "C7") (pinfunction "C7_C7") (pintype "passive"))
      (node (ref "U6") (pin "4") (pinfunction "GND1_4") (pintype "passive"))
    )
    (net (code "133") (name "GND_USB") (class "Default")
      (node (ref "C64") (pin "1") (pinfunction "1_1") (pintype "passive"))
      (node (ref "C65") (pin "1") (pinfunction "1_1") (pintype "passive"))
      (node (ref "C66") (pin "1") (pinfunction "1_1") (pintype "passive"))
      (node (ref "C67") (pin "1") (pinfunction "1_1") (pintype "passive"))
      (node (ref "C68") (pin "1") (pinfunction "1_1") (pintype "passive"))
      (node (ref "J6") (pin "4") (pinfunction "4_4") (pintype "passive"))
      (node (ref "J6") (pin "5") (pinfunction "5_5") (pintype "passive"))
      (node (ref "J6") (pin "6") (pinfunction "6_6") (pintype "passive"))
      (node (ref "LD3") (pin "1") (pinfunction "C_1") (pintype "passive"))
      (node (ref "U6") (pin "5") (pinfunction "GND2_5") (pintype "power_in"))
      (node (ref "U7") (pin "0") (pinfunction "TP_0") (pintype "passive"))
      (node (ref "U7") (pin "3") (pinfunction "GND_3") (pintype "passive"))
    )
    (net (code "134") (name "Net-(LD1-A)") (class "Default")
      (node (ref "LD1") (pin "2") (pinfunction "A_2") (pintype "passive"))
      (node (ref "R25") (pin "1") (pinfunction "1_1") (pintype "passive"))
    )
    (net (code "135") (name "Net-(LD2-A)") (class "Default")
      (node (ref "LD2") (pin "2") (pinfunction "A_2") (pintype "passive"))
      (node (ref "R26") (pin "1") (pinfunction "1_1") (pintype "passive"))
    )
    (net (code "136") (name "Net-(LD3-A)") (class "Default")
      (node (ref "LD3") (pin "2") (pinfunction "A_2") (pintype "passive"))
      (node (ref "R29") (pin "1") (pinfunction "1_1") (pintype "passive"))
    )
    (net (code "137") (name "Net-(U7-RTSb)") (class "Default")
      (node (ref "R27") (pin "1") (pinfunction "1_1") (pintype "passive"))
      (node (ref "U7") (pin "9") (pinfunction "RTSb_9") (pintype "passive"))
    )
    (net (code "138") (name "Net-(U7-SUSPENDb)") (class "Default")
      (node (ref "R29") (pin "2") (pinfunction "2_2") (pintype "passive"))
      (node (ref "U7") (pin "11") (pinfunction "SUSPENDb_11") (pintype "passive"))
    )
    (net (code "139") (name "Net-(U7-VREGIN)") (class "Default")
      (node (ref "R28") (pin "2") (pinfunction "2_2") (pintype "passive"))
      (node (ref "U7") (pin "7") (pinfunction "VREGIN_7") (pintype "passive"))
    )
    (net (code "140") (name "unconnected-(U7-CHR0-Pad15)") (class "Default")
      (node (ref "U7") (pin "15") (pinfunction "CHR0_15") (pintype "passive+no_connect"))
    )
    (net (code "141") (name "unconnected-(U7-CHR1-Pad14)") (class "Default")
      (node (ref "U7") (pin "14") (pinfunction "CHR1_14") (pintype "passive+no_connect"))
    )
    (net (code "142") (name "unconnected-(U7-CHREN-Pad13)") (class "Default")
      (node (ref "U7") (pin "13") (pinfunction "CHREN_13") (pintype "passive+no_connect"))
    )
    (net (code "143") (name "unconnected-(U7-CTS-Pad23)") (class "Default")
      (node (ref "U7") (pin "23") (pinfunction "CTS_23") (pintype "passive+no_connect"))
    )
    (net (code "144") (name "unconnected-(U7-DCD-Pad1)") (class "Default")
      (node (ref "U7") (pin "1") (pinfunction "DCD_1") (pintype "passive+no_connect"))
    )
    (net (code "145") (name "unconnected-(U7-DSR-Pad27)") (class "Default")
      (node (ref "U7") (pin "27") (pinfunction "DSR_27") (pintype "passive+no_connect"))
    )
    (net (code "146") (name "unconnected-(U7-DTR-Pad28)") (class "Default")
      (node (ref "U7") (pin "28") (pinfunction "DTR_28") (pintype "passive+no_connect"))
    )
    (net (code "147") (name "unconnected-(U7-GPIO0{slash}TXT-Pad19)") (class "Default")
      (node (ref "U7") (pin "19") (pinfunction "GPIO0/TXT_19") (pintype "passive+no_connect"))
    )
    (net (code "148") (name "unconnected-(U7-GPIO1{slash}RXT-Pad18)") (class "Default")
      (node (ref "U7") (pin "18") (pinfunction "GPIO1/RXT_18") (pintype "passive+no_connect"))
    )
    (net (code "149") (name "unconnected-(U7-GPIO2{slash}RS485-Pad17)") (class "Default")
      (node (ref "U7") (pin "17") (pinfunction "GPIO2/RS485_17") (pintype "passive+no_connect"))
    )
    (net (code "150") (name "unconnected-(U7-GPIO3{slash}WAKEUP-Pad16)") (class "Default")
      (node (ref "U7") (pin "16") (pinfunction "GPIO3/WAKEUP_16") (pintype "passive+no_connect"))
    )
    (net (code "151") (name "unconnected-(U7-GPIO4-Pad22)") (class "Default")
      (node (ref "U7") (pin "22") (pinfunction "GPIO4_22") (pintype "passive+no_connect"))
    )
    (net (code "152") (name "unconnected-(U7-GPIO5-Pad21)") (class "Default")
      (node (ref "U7") (pin "21") (pinfunction "GPIO5_21") (pintype "passive+no_connect"))
    )
    (net (code "153") (name "unconnected-(U7-GPIO6-Pad20)") (class "Default")
      (node (ref "U7") (pin "20") (pinfunction "GPIO6_20") (pintype "passive+no_connect"))
    )
    (net (code "154") (name "unconnected-(U7-NC-Pad10)") (class "Default")
      (node (ref "U7") (pin "10") (pinfunction "NC_10") (pintype "passive+no_connect"))
    )
    (net (code "155") (name "unconnected-(U7-RI{slash}CLK-Pad2)") (class "Default")
      (node (ref "U7") (pin "2") (pinfunction "RI/CLK_2") (pintype "passive+no_connect"))
    )
    (net (code "156") (name "unconnected-(U7-RTS-Pad24)") (class "Default")
      (node (ref "U7") (pin "24") (pinfunction "RTS_24") (pintype "passive+no_connect"))
    )
    (net (code "157") (name "unconnected-(U7-SUSPEND-Pad12)") (class "Default")
      (node (ref "U7") (pin "12") (pinfunction "SUSPEND_12") (pintype "passive+no_connect"))
    )
  )
)
